# 3filter.net
KiCad netlist of a schematic drawn in EAGLE
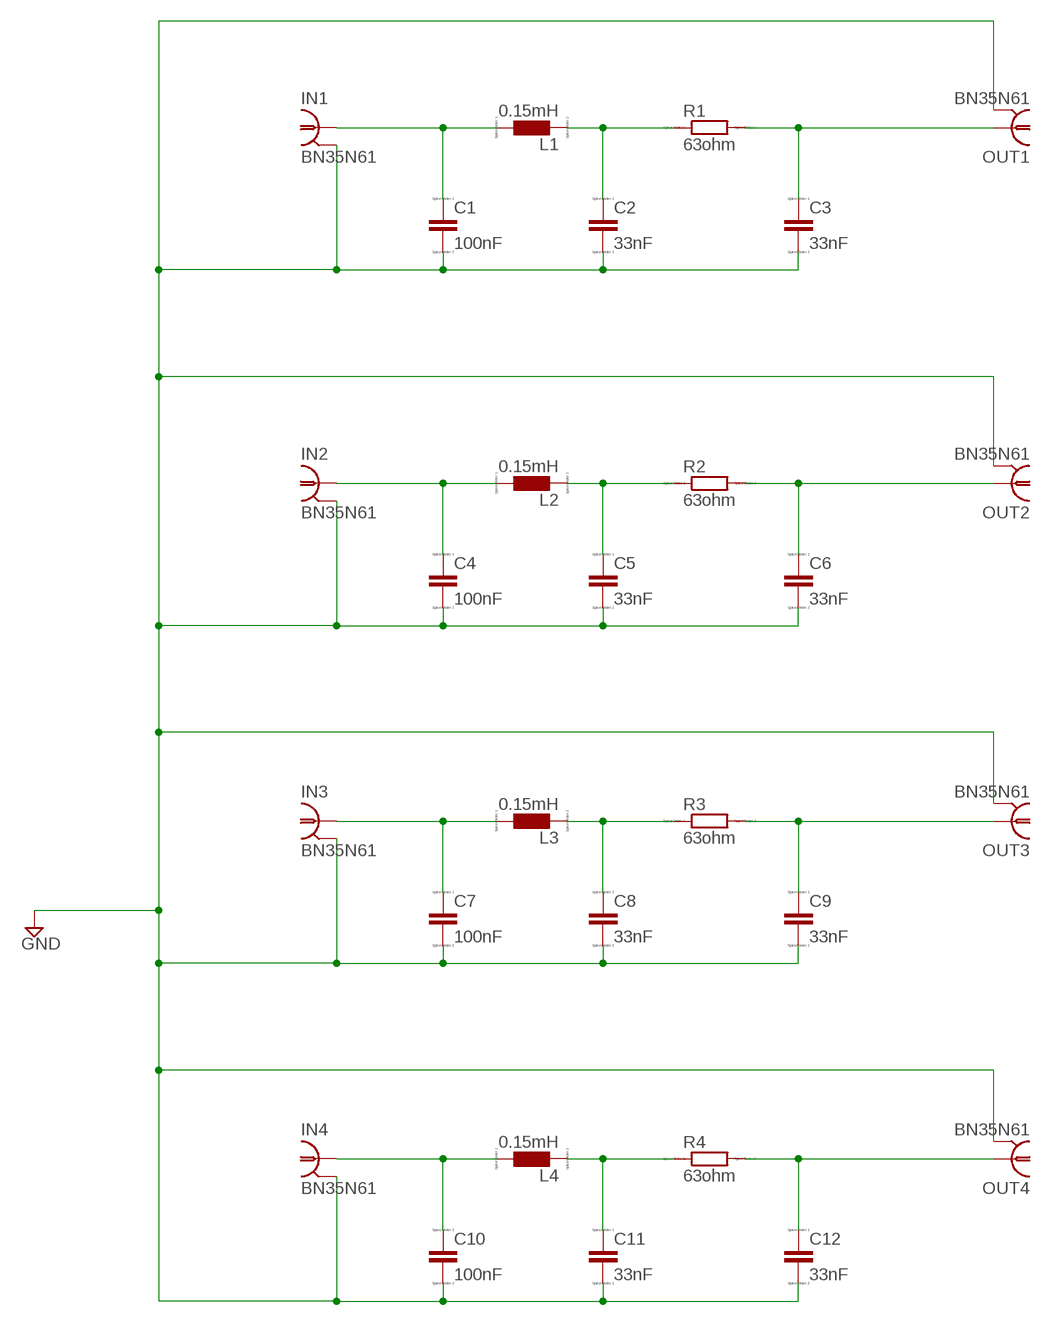
[diagram p0: schematic, sheet 1]

(export (version "E")
  (design (tool "Eeschema 10.0.6"))
  (components
    (comp (ref "C1")
      (value "100nF")
      (footprint "eagle-import:C1210")
      (libsource (lib "eagle-import") (part "CC1210"))
    )
    (comp (ref "C2")
      (value "33nF")
      (footprint "eagle-import:C1210")
      (libsource (lib "eagle-import") (part "CC1210"))
    )
    (comp (ref "C3")
      (value "33nF")
      (footprint "eagle-import:C1210")
      (libsource (lib "eagle-import") (part "CC1210"))
    )
    (comp (ref "C4")
      (value "100nF")
      (footprint "eagle-import:C1210")
      (libsource (lib "eagle-import") (part "CC1210"))
    )
    (comp (ref "C5")
      (value "33nF")
      (footprint "eagle-import:C1210")
      (libsource (lib "eagle-import") (part "CC1210"))
    )
    (comp (ref "C6")
      (value "33nF")
      (footprint "eagle-import:C1210")
      (libsource (lib "eagle-import") (part "CC1210"))
    )
    (comp (ref "C7")
      (value "100nF")
      (footprint "eagle-import:C1210")
      (libsource (lib "eagle-import") (part "CC1210"))
    )
    (comp (ref "C8")
      (value "33nF")
      (footprint "eagle-import:C1210")
      (libsource (lib "eagle-import") (part "CC1210"))
    )
    (comp (ref "C9")
      (value "33nF")
      (footprint "eagle-import:C1210")
      (libsource (lib "eagle-import") (part "CC1210"))
    )
    (comp (ref "C10")
      (value "100nF")
      (footprint "eagle-import:C1210")
      (libsource (lib "eagle-import") (part "CC1210"))
    )
    (comp (ref "C11")
      (value "33nF")
      (footprint "eagle-import:C1210")
      (libsource (lib "eagle-import") (part "CC1210"))
    )
    (comp (ref "C12")
      (value "33nF")
      (footprint "eagle-import:C1210")
      (libsource (lib "eagle-import") (part "CC1210"))
    )
    (comp (ref "IN1")
      (value "BN35N61")
      (footprint "eagle-import:B35N61")
      (libsource (lib "eagle-import") (part "BN35N61"))
    )
    (comp (ref "IN2")
      (value "BN35N61")
      (footprint "eagle-import:B35N61")
      (libsource (lib "eagle-import") (part "BN35N61"))
    )
    (comp (ref "IN3")
      (value "BN35N61")
      (footprint "eagle-import:B35N61")
      (libsource (lib "eagle-import") (part "BN35N61"))
    )
    (comp (ref "IN4")
      (value "BN35N61")
      (footprint "eagle-import:B35N61")
      (libsource (lib "eagle-import") (part "BN35N61"))
    )
    (comp (ref "L1")
      (value "0.15mH")
      (footprint "eagle-import:L1812")
      (libsource (lib "eagle-import") (part "L"))
    )
    (comp (ref "L2")
      (value "0.15mH")
      (footprint "eagle-import:L1812")
      (libsource (lib "eagle-import") (part "L"))
    )
    (comp (ref "L3")
      (value "0.15mH")
      (footprint "eagle-import:L1812")
      (libsource (lib "eagle-import") (part "L"))
    )
    (comp (ref "L4")
      (value "0.15mH")
      (footprint "eagle-import:L1812")
      (libsource (lib "eagle-import") (part "L"))
    )
    (comp (ref "OUT1")
      (value "BN35N61")
      (footprint "eagle-import:B35N61")
      (libsource (lib "eagle-import") (part "BN35N61"))
    )
    (comp (ref "OUT2")
      (value "BN35N61")
      (footprint "eagle-import:B35N61")
      (libsource (lib "eagle-import") (part "BN35N61"))
    )
    (comp (ref "OUT3")
      (value "BN35N61")
      (footprint "eagle-import:B35N61")
      (libsource (lib "eagle-import") (part "BN35N61"))
    )
    (comp (ref "OUT4")
      (value "BN35N61")
      (footprint "eagle-import:B35N61")
      (libsource (lib "eagle-import") (part "BN35N61"))
    )
    (comp (ref "R1")
      (value "63ohm")
      (footprint "eagle-import:R0805")
      (libsource (lib "eagle-import") (part "R"))
    )
    (comp (ref "R2")
      (value "63ohm")
      (footprint "eagle-import:R0805")
      (libsource (lib "eagle-import") (part "R"))
    )
    (comp (ref "R3")
      (value "63ohm")
      (footprint "eagle-import:R0805")
      (libsource (lib "eagle-import") (part "R"))
    )
    (comp (ref "R4")
      (value "63ohm")
      (footprint "eagle-import:R0805")
      (libsource (lib "eagle-import") (part "R"))
    )
  )
  (nets
    (net (code "1") (name "GND") (class "Default")
      (node (ref "C1") (pin "2") (pinfunction "2_2") (pintype "passive"))
      (node (ref "C10") (pin "2") (pinfunction "2_2") (pintype "passive"))
      (node (ref "C11") (pin "2") (pinfunction "2_2") (pintype "passive"))
      (node (ref "C12") (pin "2") (pinfunction "2_2") (pintype "passive"))
      (node (ref "C2") (pin "2") (pinfunction "2_2") (pintype "passive"))
      (node (ref "C3") (pin "2") (pinfunction "2_2") (pintype "passive"))
      (node (ref "C4") (pin "2") (pinfunction "2_2") (pintype "passive"))
      (node (ref "C5") (pin "2") (pinfunction "2_2") (pintype "passive"))
      (node (ref "C6") (pin "2") (pinfunction "2_2") (pintype "passive"))
      (node (ref "C7") (pin "2") (pinfunction "2_2") (pintype "passive"))
      (node (ref "C8") (pin "2") (pinfunction "2_2") (pintype "passive"))
      (node (ref "C9") (pin "2") (pinfunction "2_2") (pintype "passive"))
      (node (ref "IN1") (pin "2") (pinfunction "2_2") (pintype "passive"))
      (node (ref "IN1") (pin "3") (pinfunction "2_3") (pintype "passive"))
      (node (ref "IN1") (pin "4") (pinfunction "2_4") (pintype "passive"))
      (node (ref "IN1") (pin "5") (pinfunction "2_5") (pintype "passive"))
      (node (ref "IN2") (pin "2") (pinfunction "2_2") (pintype "passive"))
      (node (ref "IN2") (pin "3") (pinfunction "2_3") (pintype "passive"))
      (node (ref "IN2") (pin "4") (pinfunction "2_4") (pintype "passive"))
      (node (ref "IN2") (pin "5") (pinfunction "2_5") (pintype "passive"))
      (node (ref "IN3") (pin "2") (pinfunction "2_2") (pintype "passive"))
      (node (ref "IN3") (pin "3") (pinfunction "2_3") (pintype "passive"))
      (node (ref "IN3") (pin "4") (pinfunction "2_4") (pintype "passive"))
      (node (ref "IN3") (pin "5") (pinfunction "2_5") (pintype "passive"))
      (node (ref "IN4") (pin "2") (pinfunction "2_2") (pintype "passive"))
      (node (ref "IN4") (pin "3") (pinfunction "2_3") (pintype "passive"))
      (node (ref "IN4") (pin "4") (pinfunction "2_4") (pintype "passive"))
      (node (ref "IN4") (pin "5") (pinfunction "2_5") (pintype "passive"))
      (node (ref "OUT1") (pin "2") (pinfunction "2_2") (pintype "passive"))
      (node (ref "OUT1") (pin "3") (pinfunction "2_3") (pintype "passive"))
      (node (ref "OUT1") (pin "4") (pinfunction "2_4") (pintype "passive"))
      (node (ref "OUT1") (pin "5") (pinfunction "2_5") (pintype "passive"))
      (node (ref "OUT2") (pin "2") (pinfunction "2_2") (pintype "passive"))
      (node (ref "OUT2") (pin "3") (pinfunction "2_3") (pintype "passive"))
      (node (ref "OUT2") (pin "4") (pinfunction "2_4") (pintype "passive"))
      (node (ref "OUT2") (pin "5") (pinfunction "2_5") (pintype "passive"))
      (node (ref "OUT3") (pin "2") (pinfunction "2_2") (pintype "passive"))
      (node (ref "OUT3") (pin "3") (pinfunction "2_3") (pintype "passive"))
      (node (ref "OUT3") (pin "4") (pinfunction "2_4") (pintype "passive"))
      (node (ref "OUT3") (pin "5") (pinfunction "2_5") (pintype "passive"))
      (node (ref "OUT4") (pin "2") (pinfunction "2_2") (pintype "passive"))
      (node (ref "OUT4") (pin "3") (pinfunction "2_3") (pintype "passive"))
      (node (ref "OUT4") (pin "4") (pinfunction "2_4") (pintype "passive"))
      (node (ref "OUT4") (pin "5") (pinfunction "2_5") (pintype "passive"))
    )
    (net (code "2") (name "Net-(C1-Pad1)") (class "Default")
      (node (ref "C1") (pin "1") (pinfunction "1_1") (pintype "passive"))
      (node (ref "IN1") (pin "1") (pinfunction "1_1") (pintype "passive"))
      (node (ref "L1") (pin "1") (pinfunction "1_1") (pintype "passive"))
    )
    (net (code "3") (name "Net-(C2-Pad1)") (class "Default")
      (node (ref "C2") (pin "1") (pinfunction "1_1") (pintype "passive"))
      (node (ref "L1") (pin "2") (pinfunction "2_2") (pintype "passive"))
      (node (ref "R1") (pin "1") (pinfunction "1_1") (pintype "passive"))
    )
    (net (code "4") (name "Net-(C3-Pad1)") (class "Default")
      (node (ref "C3") (pin "1") (pinfunction "1_1") (pintype "passive"))
      (node (ref "OUT1") (pin "1") (pinfunction "1_1") (pintype "passive"))
      (node (ref "R1") (pin "2") (pinfunction "2_2") (pintype "passive"))
    )
    (net (code "5") (name "Net-(C4-Pad1)") (class "Default")
      (node (ref "C4") (pin "1") (pinfunction "1_1") (pintype "passive"))
      (node (ref "IN2") (pin "1") (pinfunction "1_1") (pintype "passive"))
      (node (ref "L2") (pin "1") (pinfunction "1_1") (pintype "passive"))
    )
    (net (code "6") (name "Net-(C5-Pad1)") (class "Default")
      (node (ref "C5") (pin "1") (pinfunction "1_1") (pintype "passive"))
      (node (ref "L2") (pin "2") (pinfunction "2_2") (pintype "passive"))
      (node (ref "R2") (pin "1") (pinfunction "1_1") (pintype "passive"))
    )
    (net (code "7") (name "Net-(C6-Pad1)") (class "Default")
      (node (ref "C6") (pin "1") (pinfunction "1_1") (pintype "passive"))
      (node (ref "OUT2") (pin "1") (pinfunction "1_1") (pintype "passive"))
      (node (ref "R2") (pin "2") (pinfunction "2_2") (pintype "passive"))
    )
    (net (code "8") (name "Net-(C7-Pad1)") (class "Default")
      (node (ref "C7") (pin "1") (pinfunction "1_1") (pintype "passive"))
      (node (ref "IN3") (pin "1") (pinfunction "1_1") (pintype "passive"))
      (node (ref "L3") (pin "1") (pinfunction "1_1") (pintype "passive"))
    )
    (net (code "9") (name "Net-(C8-Pad1)") (class "Default")
      (node (ref "C8") (pin "1") (pinfunction "1_1") (pintype "passive"))
      (node (ref "L3") (pin "2") (pinfunction "2_2") (pintype "passive"))
      (node (ref "R3") (pin "1") (pinfunction "1_1") (pintype "passive"))
    )
    (net (code "10") (name "Net-(C9-Pad1)") (class "Default")
      (node (ref "C9") (pin "1") (pinfunction "1_1") (pintype "passive"))
      (node (ref "OUT3") (pin "1") (pinfunction "1_1") (pintype "passive"))
      (node (ref "R3") (pin "2") (pinfunction "2_2") (pintype "passive"))
    )
    (net (code "11") (name "Net-(C10-Pad1)") (class "Default")
      (node (ref "C10") (pin "1") (pinfunction "1_1") (pintype "passive"))
      (node (ref "IN4") (pin "1") (pinfunction "1_1") (pintype "passive"))
      (node (ref "L4") (pin "1") (pinfunction "1_1") (pintype "passive"))
    )
    (net (code "12") (name "Net-(C11-Pad1)") (class "Default")
      (node (ref "C11") (pin "1") (pinfunction "1_1") (pintype "passive"))
      (node (ref "L4") (pin "2") (pinfunction "2_2") (pintype "passive"))
      (node (ref "R4") (pin "1") (pinfunction "1_1") (pintype "passive"))
    )
    (net (code "13") (name "Net-(C12-Pad1)") (class "Default")
      (node (ref "C12") (pin "1") (pinfunction "1_1") (pintype "passive"))
      (node (ref "OUT4") (pin "1") (pinfunction "1_1") (pintype "passive"))
      (node (ref "R4") (pin "2") (pinfunction "2_2") (pintype "passive"))
    )
  )
)
